# PCB_STM32.net
KiCad netlist of a schematic drawn in Altium Designer
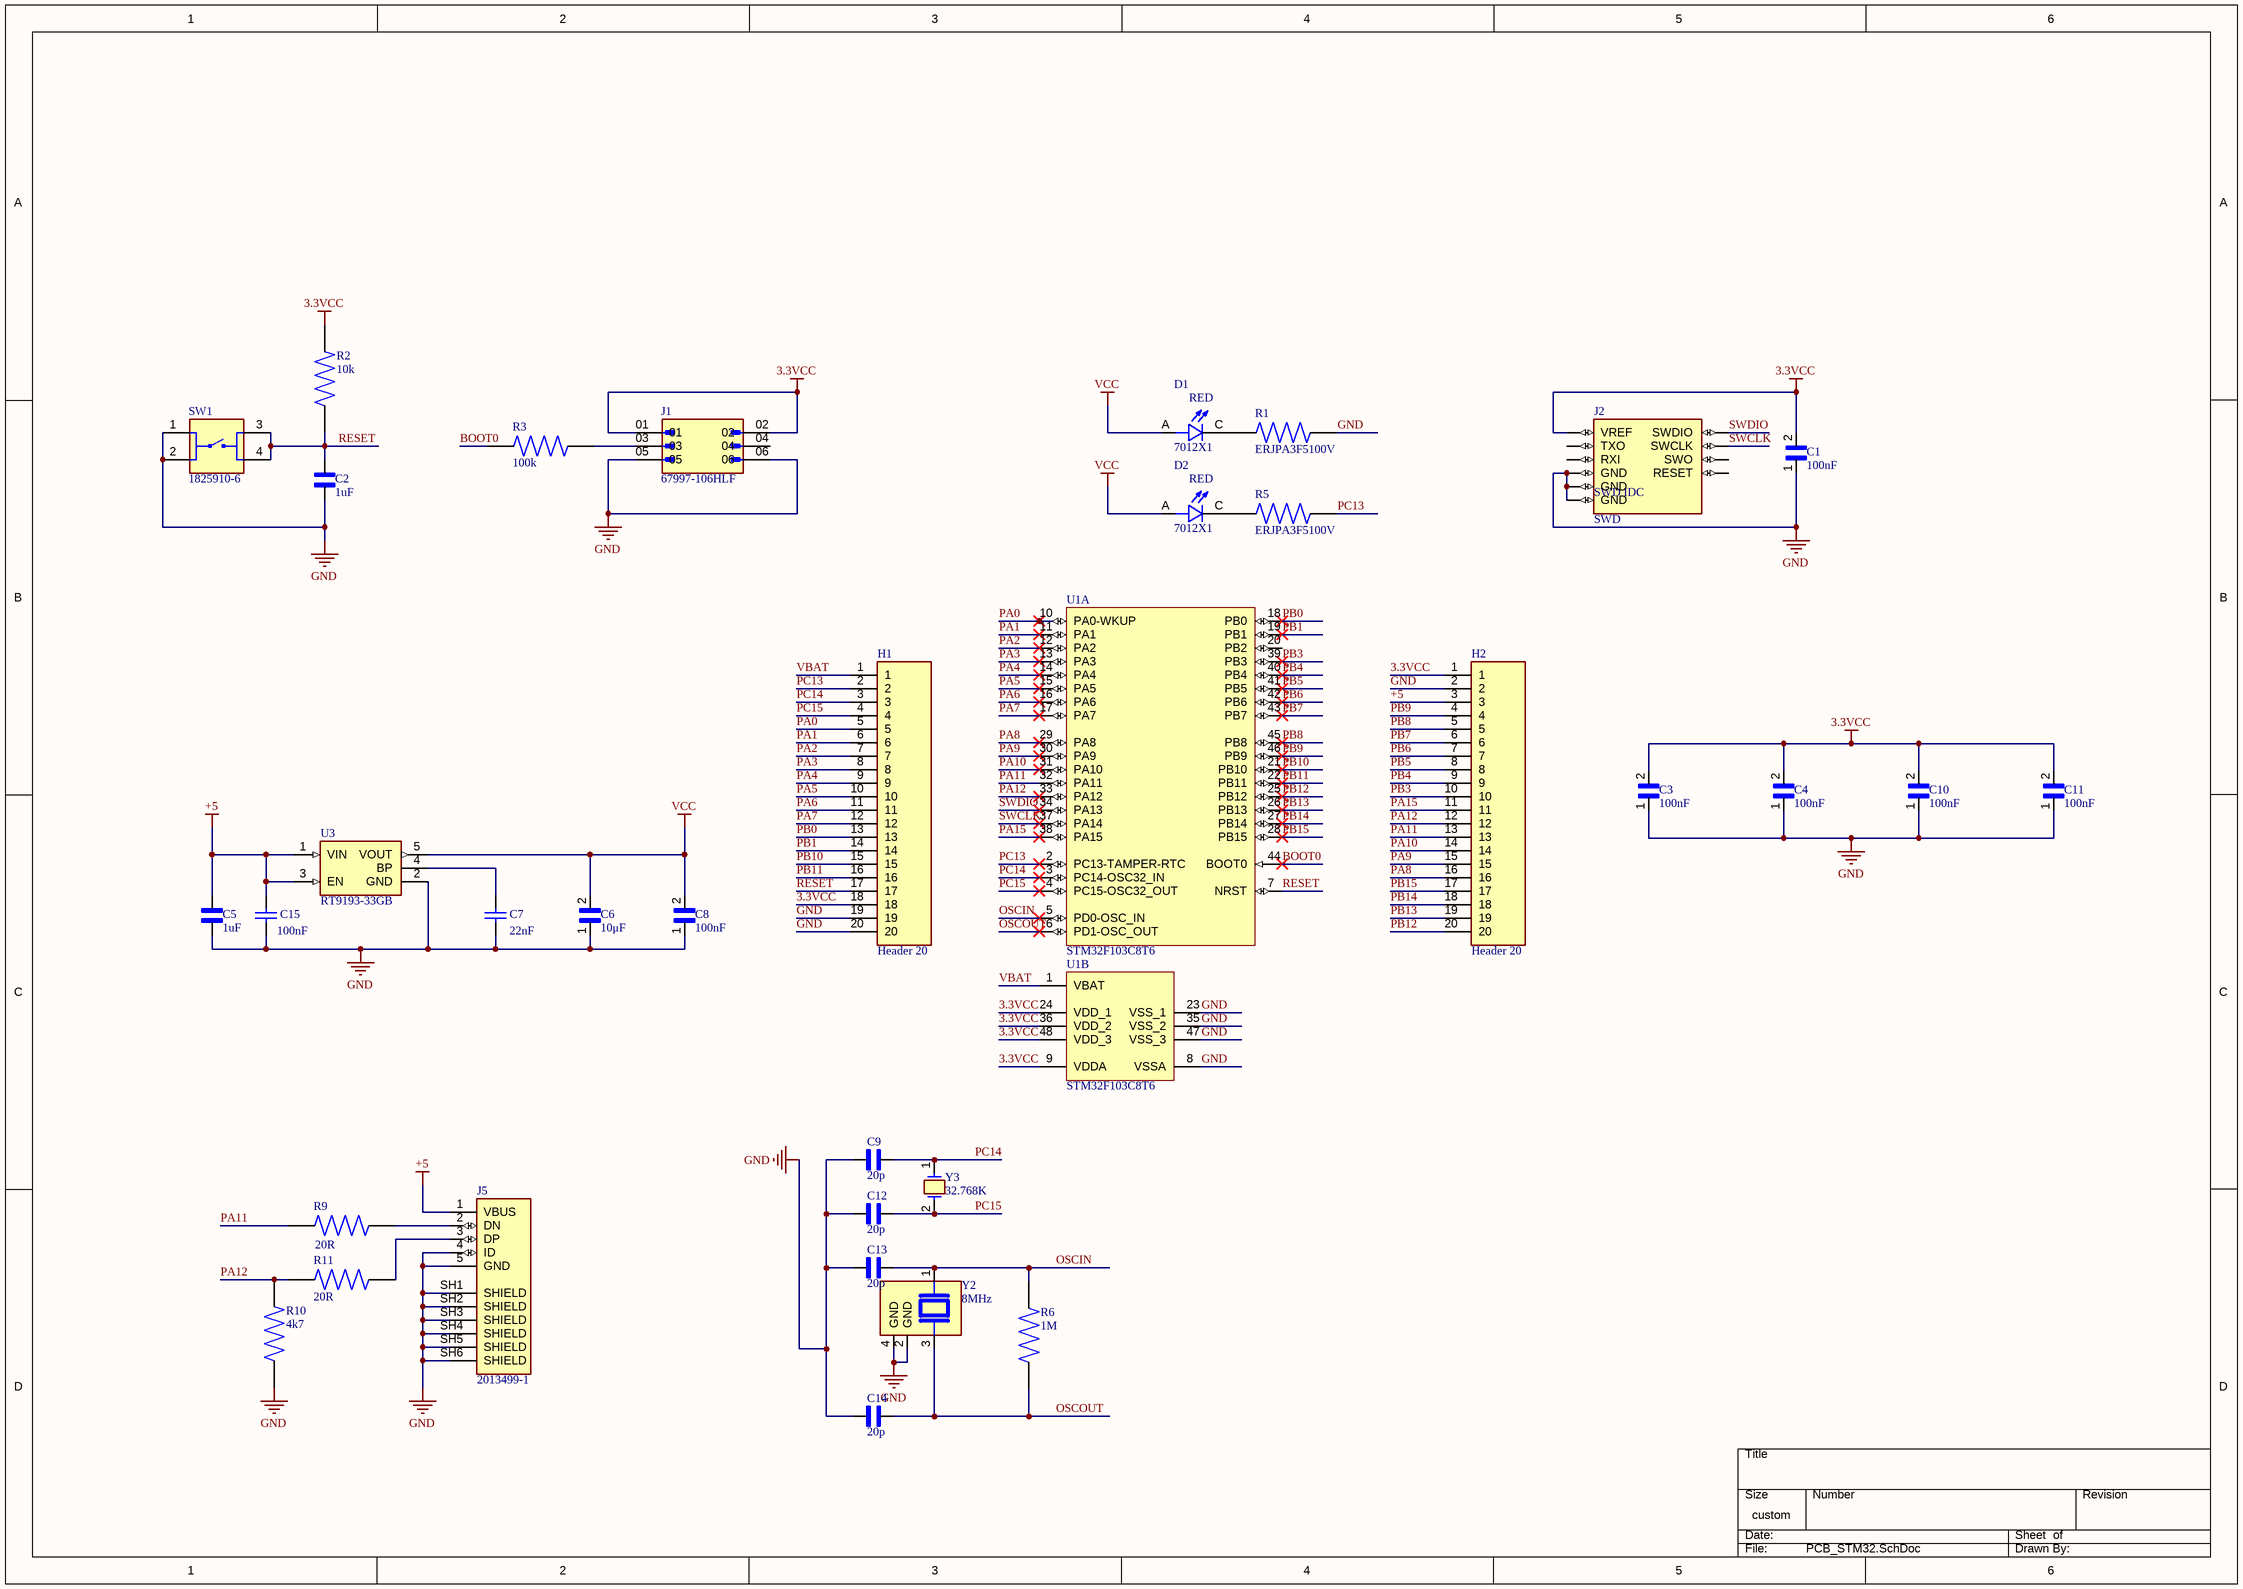
[diagram p0: PCB_STM32.SchDoc]

(export (version "E")
  (design (tool "Eeschema 10.0.6"))
  (components
    (comp (ref "C1")
      (value "100nF")
      (footprint "WCAP-CSGP_0201_L0.6W0.3H0.3")
      (description "0.1 ÂµF Â±10% 50V Ceramic Capacitor X7R 0805 (2012 Metric)")
      (fields (field (name "MP") "C2012X7R1H104K085AA") (field (name "MF") "TDK"))
      (libsource (lib "Cap01u") (part "C2012X7R1H104K085AA"))
    )
    (comp (ref "C2")
      (value "1uF")
      (footprint "CAPC1608X55N")
      (description "Cap Ceramic 1uF 10V X6S 10% SMD 0603 105Â°C Punched Paper T/R")
      (fields (field (name "MF") "TDK") (field (name "MP") "CGB3B3X6S1A105K055AB"))
      (libsource (lib "Cap1u") (part "CGB3B3X6S1A105K055AB"))
    )
    (comp (ref "C3")
      (value "100nF")
      (footprint "WCAP-CSGP_0201_L0.6W0.3H0.3")
      (description "0.1 ÂµF Â±10% 50V Ceramic Capacitor X7R 0805 (2012 Metric)")
      (fields (field (name "MP") "C2012X7R1H104K085AA") (field (name "MF") "TDK"))
      (libsource (lib "Cap01u") (part "C2012X7R1H104K085AA"))
    )
    (comp (ref "C4")
      (value "100nF")
      (footprint "WCAP-CSGP_0201_L0.6W0.3H0.3")
      (description "0.1 ÂµF Â±10% 50V Ceramic Capacitor X7R 0805 (2012 Metric)")
      (fields (field (name "MP") "C2012X7R1H104K085AA") (field (name "MF") "TDK"))
      (libsource (lib "Cap01u") (part "C2012X7R1H104K085AA"))
    )
    (comp (ref "C5")
      (value "1uF")
      (footprint "CAPC1608X55N")
      (description "Cap Ceramic 1uF 10V X6S 10% SMD 0603 105Â°C Punched Paper T/R")
      (fields (field (name "MF") "TDK") (field (name "MP") "CGB3B3X6S1A105K055AB"))
      (libsource (lib "Cap1u") (part "CGB3B3X6S1A105K055AB"))
    )
    (comp (ref "C6")
      (value "10μF")
      (footprint "WCAP-CSGP_0402_L1W0.5H0.5")
      (description "10ÂµF Â±20% 16V Ceramic Capacitor X5R 0805 (2012 Metric)")
      (fields (field (name "MF") "TDK") (field (name "MP") "C2012X5R1C106M085AC"))
      (libsource (lib "Cap10u") (part "C2012X5R1C106M085AC"))
    )
    (comp (ref "C7")
      (value "22nF")
      (footprint "WCAP-CSGP_1206_L3.2W1.6H1.6")
      (description "WCAP-CSGP Multilayer Ceramic Chip Capacitor, General Purpose, size 1206, NP0, 22nF, 10V")
      (fields
        (field (name "MANUFACTURER PART NUMBER") "885012008009")
        (field (name "MANUFACTURER") "Wurth Elektronik")
      )
      (libsource (lib "Cap100n") (part "885012008009"))
    )
    (comp (ref "C8")
      (value "100nF")
      (footprint "WCAP-CSGP_0201_L0.6W0.3H0.3")
      (description "0.1 ÂµF Â±10% 50V Ceramic Capacitor X7R 0805 (2012 Metric)")
      (fields (field (name "MP") "C2012X7R1H104K085AA") (field (name "MF") "TDK"))
      (libsource (lib "Cap01u") (part "C2012X7R1H104K085AA"))
    )
    (comp (ref "C9")
      (value "20p")
      (footprint "CAPC0603X33N")
      (description "SMD capacitor C0G(EIA) with capacitance 20pF Tol.5%. Rated voltage 50Vdc 125C")
      (fields (field (name "MF") "Murata Electronics") (field (name "MP") "GRM0335C1H200JA01D"))
      (libsource (lib "Cap20pF") (part "GRM0335C1H200JA01D"))
    )
    (comp (ref "C10")
      (value "100nF")
      (footprint "WCAP-CSGP_0201_L0.6W0.3H0.3")
      (description "0.1 ÂµF Â±10% 50V Ceramic Capacitor X7R 0805 (2012 Metric)")
      (fields (field (name "MP") "C2012X7R1H104K085AA") (field (name "MF") "TDK"))
      (libsource (lib "Cap01u") (part "C2012X7R1H104K085AA"))
    )
    (comp (ref "C11")
      (value "100nF")
      (footprint "WCAP-CSGP_0201_L0.6W0.3H0.3")
      (description "0.1 ÂµF Â±10% 50V Ceramic Capacitor X7R 0805 (2012 Metric)")
      (fields (field (name "MP") "C2012X7R1H104K085AA") (field (name "MF") "TDK"))
      (libsource (lib "Cap01u") (part "C2012X7R1H104K085AA"))
    )
    (comp (ref "C12")
      (value "20p")
      (footprint "CAPC0603X33N")
      (description "SMD capacitor C0G(EIA) with capacitance 20pF Tol.5%. Rated voltage 50Vdc 125C")
      (fields (field (name "MF") "Murata Electronics") (field (name "MP") "GRM0335C1H200JA01D"))
      (libsource (lib "Cap20pF") (part "GRM0335C1H200JA01D"))
    )
    (comp (ref "C13")
      (value "20p")
      (footprint "CAPC0603X33N")
      (description "SMD capacitor C0G(EIA) with capacitance 20pF Tol.5%. Rated voltage 50Vdc 125C")
      (fields (field (name "MF") "Murata Electronics") (field (name "MP") "GRM0335C1H200JA01D"))
      (libsource (lib "Cap20pF") (part "GRM0335C1H200JA01D"))
    )
    (comp (ref "C14")
      (value "20p")
      (footprint "CAPC0603X33N")
      (description "SMD capacitor C0G(EIA) with capacitance 20pF Tol.5%. Rated voltage 50Vdc 125C")
      (fields (field (name "MF") "Murata Electronics") (field (name "MP") "GRM0335C1H200JA01D"))
      (libsource (lib "Cap20pF") (part "GRM0335C1H200JA01D"))
    )
    (comp (ref "C15")
      (value "100nF")
      (footprint "WCAP-CSGP_0201_L0.6W0.3H0.3")
      (description "WCAP-CSGP Multilayer Ceramic Chip Capacitor, General Purpose, size 0201, X5R Class II, 100nF, 16V")
      (fields
        (field (name "MANUFACTURER PART NUMBER") "885012104001")
        (field (name "MANUFACTURER") "Wurth Elektronik")
      )
      (libsource (lib "Cap100n") (part "885012104001"))
    )
    (comp (ref "D1")
      (value "7012X1")
      (footprint "LED_7012X1")
      (description "Red - LED Indication - Discrete 1.7V 0805 (2012 Metric)")
      (fields (field (name "MF") "VCC"))
      (libsource (lib "RedLed") (part "7012X1"))
    )
    (comp (ref "D2")
      (value "7012X1")
      (footprint "LED_7012X1")
      (description "Red - LED Indication - Discrete 1.7V 0805 (2012 Metric)")
      (fields (field (name "MF") "VCC"))
      (libsource (lib "RedLed") (part "7012X1"))
    )
    (comp (ref "H1")
      (value "Header 20")
      (footprint "TE_2-640456-0")
      (description "Header Friction Lock MTA-100 20 250VAC Polyester Tin Copper Alloy Tin ¦ TE Connectivity 2-640456-0")
      (fields (field (name "MF") "TE Connectivity") (field (name "MP") "2-640456-0"))
      (libsource (lib "Header20") (part "2-640456-0"))
    )
    (comp (ref "H2")
      (value "Header 20")
      (footprint "TE_2-640456-0")
      (description "Header Friction Lock MTA-100 20 250VAC Polyester Tin Copper Alloy Tin ¦ TE Connectivity 2-640456-0")
      (fields (field (name "MF") "TE Connectivity") (field (name "MP") "2-640456-0"))
      (libsource (lib "Header20") (part "2-640456-0"))
    )
    (comp (ref "J1")
      (value "67997-106HLF")
      (footprint "AMPHENOL_67997-106HLF")
      (fields (field (name "MF") "Amphenol ICC"))
      (libsource (lib "Header3x2") (part "67997-106HLF"))
    )
    (comp (ref "J2")
      (value "SWD")
      (footprint "ARM-JTAG-10-SWD-IDC")
      (description "DEBUG ADAPTER FOR ARM-USB-TINY-H")
      (fields (field (name "MF") "Olimex LTD") (field (name "MP") "ARM-JTAG-SWD"))
      (libsource (lib "SWD") (part "ARM-JTAG-SWD"))
    )
    (comp (ref "J5")
      (value "2013499-1")
      (footprint "TE_2013499-1")
      (libsource (lib "micro USB") (part "2013499-1"))
    )
    (comp (ref "R1")
      (value "ERJPA3F5100V")
      (footprint "RES_ERJPA3F5100V")
      (description "RES, THICK FILM, 510R, 1%, 0.25W, 0603")
      (fields (field (name "MF") "Panasonic") (field (name "MP") "ERJ-PA3F5100V"))
      (libsource (lib "RES510") (part "ERJPA3F5100V"))
    )
    (comp (ref "R2")
      (value "10k")
      (footprint "RESC2012X60N")
      (description "10 kOhms Â±1% 0.125W, 1/8W Chip Resistor 0805 (2012 Metric) Moisture Resistant Thick Film")
      (fields (field (name "MF") "Yageo") (field (name "MP") "RC0805FR-0710KL"))
      (libsource (lib "RES10k") (part "RC0805FR-0710KL"))
    )
    (comp (ref "R3")
      (value "100k")
      (footprint "RESC2012X60N")
      (description "100 kOhms Â±1% 0.125W, 1/8W Chip Resistor 0805 (2012 Metric) Moisture Resistant Thick Film")
      (fields (field (name "MF") "Yageo") (field (name "MP") "RC0805FR-07100KL"))
      (libsource (lib "RES100k") (part "RC0805FR-07100KL"))
    )
    (comp (ref "R5")
      (value "ERJPA3F5100V")
      (footprint "RES_ERJPA3F5100V")
      (description "RES, THICK FILM, 510R, 1%, 0.25W, 0603")
      (fields (field (name "MF") "Panasonic") (field (name "MP") "ERJ-PA3F5100V"))
      (libsource (lib "RES510") (part "ERJPA3F5100V"))
    )
    (comp (ref "R6")
      (value "1M")
      (footprint "RESC2012X60N")
      (description "1 MOhms Â±1% 0.125W, 1/8W Chip Resistor 0805 (2012 Metric) Moisture Resistant Thick Film")
      (fields (field (name "MF") "Yageo") (field (name "MP") "RC0805FR-071ML"))
      (libsource (lib "RES1M") (part "RC0805FR-071ML"))
    )
    (comp (ref "R9")
      (value "20R")
      (footprint "RESC5025X120N")
      (fields (field (name "MP") "3-2176397-2"))
      (libsource (lib "RES20") (part "3-2176397-2"))
    )
    (comp (ref "R10")
      (value "4k7")
      (footprint "RESC1608X55N")
      (fields
        (field (name "MF") "TE Connectivity")
        (field (name "MP") "CRG0603F4K7")
        (field (name "TOLERANCE") "1%")
      )
      (libsource (lib "RES4.7k") (part "CRG0603F4K7"))
    )
    (comp (ref "R11")
      (value "20R")
      (footprint "RESC5025X120N")
      (fields (field (name "MP") "3-2176397-2"))
      (libsource (lib "RES20") (part "3-2176397-2"))
    )
    (comp (ref "SW1")
      (value "1825910-6")
      (footprint "SW_1825910-6-4")
      (description "Switch Push Button OFF (ON) SPST Round Button 0.05A 24VDC Momentary Contact PC Pins Thru-Hole")
      (fields (field (name "MF") "TE Connectivity") (field (name "DIGI-KEY_PART_NUMBER") "450-1650-ND"))
      (libsource (lib "Button") (part "1825910-6"))
    )
    (comp (ref "U1")
      (value "STM32F103C8T6")
      (footprint "STM-LQFP48_L")
      (libsource (lib "STM32") (part "CMP-0237-00215-3"))
    )
    (comp (ref "U3")
      (value "RT9193-33GB")
      (footprint "SOT94P279X129-5N")
      (description "Linear Voltage Regulator IC Positive Fixed 1 Output 300mA TSOT-23-5")
      (fields (field (name "MF") "Richtek USA") (field (name "DIGI-KEY_PART_NUMBER") "1028-1014-2-ND"))
      (libsource (lib "RT9193-33GB") (part "RT9193-33GB"))
    )
    (comp (ref "Y2")
      (value "8MHz")
      (footprint "XTAL_ABM3B-8.000MHZ-10-1-U-T")
      (description "8 MHz Â±10ppm Crystal 10pF 200 Ohms 4-SMD, No Lead")
      (fields (field (name "MF") "Abracon") (field (name "MP") "ABM3B-8.000MHZ-10-1-U-T"))
      (libsource (lib "Crystal 8MHz") (part "ABM3B-8.000MHZ-10-1-U-T"))
    )
    (comp (ref "Y3")
      (value "32.768K")
      (footprint "XTAL_NX3215SA-32.768K-STD-MUA-14")
      (description "32.768kHz Â±20ppm Crystal 6pF 70 kOhms 2-SMD, No Lead  MANUFACTURER: NIHON DEMPA KOGYO")
      (fields (field (name "MP") "NX3215SA-32.768K-STD-MUA-14"))
      (libsource (lib "Crystal 32.768k") (part "NX3215SA-32.768K-STD-MUA-14"))
    )
  )
  (nets
    (net (code "1") (name "+5") (class "Default")
      (node (ref "C15") (pin "2") (pinfunction "2_2") (pintype "passive"))
      (node (ref "C5") (pin "1") (pinfunction "1_1") (pintype "passive"))
      (node (ref "H2") (pin "3") (pinfunction "3_3") (pintype "passive"))
      (node (ref "J5") (pin "1") (pinfunction "VBUS_1") (pintype "power_in"))
      (node (ref "U3") (pin "1") (pinfunction "VIN_1") (pintype "input"))
      (node (ref "U3") (pin "3") (pinfunction "EN_3") (pintype "input"))
    )
    (net (code "2") (name "/BOOT0") (class "Default")
      (node (ref "R3") (pin "1") (pinfunction "1_1") (pintype "passive"))
      (node (ref "U1") (pin "44") (pinfunction "BOOT0_44") (pintype "input"))
    )
    (net (code "3") (name "/OSCIN") (class "Default")
      (node (ref "C13") (pin "2") (pinfunction "2_2") (pintype "passive"))
      (node (ref "R6") (pin "2") (pinfunction "2_2") (pintype "passive"))
      (node (ref "U1") (pin "5") (pinfunction "PD0-OSC_IN_5") (pintype "bidirectional"))
      (node (ref "Y2") (pin "1") (pinfunction "1_1") (pintype "passive"))
    )
    (net (code "4") (name "/OSCOUT") (class "Default")
      (node (ref "C14") (pin "2") (pinfunction "2_2") (pintype "passive"))
      (node (ref "R6") (pin "1") (pinfunction "1_1") (pintype "passive"))
      (node (ref "U1") (pin "6") (pinfunction "PD1-OSC_OUT_6") (pintype "bidirectional"))
      (node (ref "Y2") (pin "3") (pinfunction "2_3") (pintype "passive"))
    )
    (net (code "5") (name "/PA0") (class "Default")
      (node (ref "H1") (pin "5") (pinfunction "5_5") (pintype "passive"))
      (node (ref "U1") (pin "10") (pinfunction "PA0-WKUP_10") (pintype "bidirectional"))
    )
    (net (code "6") (name "/PA1") (class "Default")
      (node (ref "H1") (pin "6") (pinfunction "6_6") (pintype "passive"))
      (node (ref "U1") (pin "11") (pinfunction "PA1_11") (pintype "bidirectional"))
    )
    (net (code "7") (name "/PA2") (class "Default")
      (node (ref "H1") (pin "7") (pinfunction "7_7") (pintype "passive"))
      (node (ref "U1") (pin "12") (pinfunction "PA2_12") (pintype "bidirectional"))
    )
    (net (code "8") (name "/PA3") (class "Default")
      (node (ref "H1") (pin "8") (pinfunction "8_8") (pintype "passive"))
      (node (ref "U1") (pin "13") (pinfunction "PA3_13") (pintype "bidirectional"))
    )
    (net (code "9") (name "/PA4") (class "Default")
      (node (ref "H1") (pin "9") (pinfunction "9_9") (pintype "passive"))
      (node (ref "U1") (pin "14") (pinfunction "PA4_14") (pintype "bidirectional"))
    )
    (net (code "10") (name "/PA5") (class "Default")
      (node (ref "H1") (pin "10") (pinfunction "10_10") (pintype "passive"))
      (node (ref "U1") (pin "15") (pinfunction "PA5_15") (pintype "bidirectional"))
    )
    (net (code "11") (name "/PA6") (class "Default")
      (node (ref "H1") (pin "11") (pinfunction "11_11") (pintype "passive"))
      (node (ref "U1") (pin "16") (pinfunction "PA6_16") (pintype "bidirectional"))
    )
    (net (code "12") (name "/PA7") (class "Default")
      (node (ref "H1") (pin "12") (pinfunction "12_12") (pintype "passive"))
      (node (ref "U1") (pin "17") (pinfunction "PA7_17") (pintype "bidirectional"))
    )
    (net (code "13") (name "/PA8") (class "Default")
      (node (ref "H2") (pin "16") (pinfunction "16_16") (pintype "passive"))
      (node (ref "U1") (pin "29") (pinfunction "PA8_29") (pintype "bidirectional"))
    )
    (net (code "14") (name "/PA9") (class "Default")
      (node (ref "H2") (pin "15") (pinfunction "15_15") (pintype "passive"))
      (node (ref "U1") (pin "30") (pinfunction "PA9_30") (pintype "bidirectional"))
    )
    (net (code "15") (name "/PA10") (class "Default")
      (node (ref "H2") (pin "14") (pinfunction "14_14") (pintype "passive"))
      (node (ref "U1") (pin "31") (pinfunction "PA10_31") (pintype "bidirectional"))
    )
    (net (code "16") (name "/PA11") (class "Default")
      (node (ref "H2") (pin "13") (pinfunction "13_13") (pintype "passive"))
      (node (ref "R9") (pin "1") (pinfunction "1_1") (pintype "passive"))
      (node (ref "U1") (pin "32") (pinfunction "PA11_32") (pintype "bidirectional"))
    )
    (net (code "17") (name "/PA12") (class "Default")
      (node (ref "H2") (pin "12") (pinfunction "12_12") (pintype "passive"))
      (node (ref "R10") (pin "2") (pinfunction "2_2") (pintype "passive"))
      (node (ref "R11") (pin "1") (pinfunction "1_1") (pintype "passive"))
      (node (ref "U1") (pin "33") (pinfunction "PA12_33") (pintype "bidirectional"))
    )
    (net (code "18") (name "/PA15") (class "Default")
      (node (ref "H2") (pin "11") (pinfunction "11_11") (pintype "passive"))
      (node (ref "U1") (pin "38") (pinfunction "PA15_38") (pintype "bidirectional"))
    )
    (net (code "19") (name "/PB0") (class "Default")
      (node (ref "H1") (pin "13") (pinfunction "13_13") (pintype "passive"))
      (node (ref "U1") (pin "18") (pinfunction "PB0_18") (pintype "bidirectional"))
    )
    (net (code "20") (name "/PB1") (class "Default")
      (node (ref "H1") (pin "14") (pinfunction "14_14") (pintype "passive"))
      (node (ref "U1") (pin "19") (pinfunction "PB1_19") (pintype "bidirectional"))
    )
    (net (code "21") (name "/PB3") (class "Default")
      (node (ref "H2") (pin "10") (pinfunction "10_10") (pintype "passive"))
      (node (ref "U1") (pin "39") (pinfunction "PB3_39") (pintype "bidirectional"))
    )
    (net (code "22") (name "/PB4") (class "Default")
      (node (ref "H2") (pin "9") (pinfunction "9_9") (pintype "passive"))
      (node (ref "U1") (pin "40") (pinfunction "PB4_40") (pintype "bidirectional"))
    )
    (net (code "23") (name "/PB5") (class "Default")
      (node (ref "H2") (pin "8") (pinfunction "8_8") (pintype "passive"))
      (node (ref "U1") (pin "41") (pinfunction "PB5_41") (pintype "bidirectional"))
    )
    (net (code "24") (name "/PB6") (class "Default")
      (node (ref "H2") (pin "7") (pinfunction "7_7") (pintype "passive"))
      (node (ref "U1") (pin "42") (pinfunction "PB6_42") (pintype "bidirectional"))
    )
    (net (code "25") (name "/PB7") (class "Default")
      (node (ref "H2") (pin "6") (pinfunction "6_6") (pintype "passive"))
      (node (ref "U1") (pin "43") (pinfunction "PB7_43") (pintype "bidirectional"))
    )
    (net (code "26") (name "/PB8") (class "Default")
      (node (ref "H2") (pin "5") (pinfunction "5_5") (pintype "passive"))
      (node (ref "U1") (pin "45") (pinfunction "PB8_45") (pintype "bidirectional"))
    )
    (net (code "27") (name "/PB9") (class "Default")
      (node (ref "H2") (pin "4") (pinfunction "4_4") (pintype "passive"))
      (node (ref "U1") (pin "46") (pinfunction "PB9_46") (pintype "bidirectional"))
    )
    (net (code "28") (name "/PB10") (class "Default")
      (node (ref "H1") (pin "15") (pinfunction "15_15") (pintype "passive"))
      (node (ref "U1") (pin "21") (pinfunction "PB10_21") (pintype "bidirectional"))
    )
    (net (code "29") (name "/PB11") (class "Default")
      (node (ref "H1") (pin "16") (pinfunction "16_16") (pintype "passive"))
      (node (ref "U1") (pin "22") (pinfunction "PB11_22") (pintype "bidirectional"))
    )
    (net (code "30") (name "/PB12") (class "Default")
      (node (ref "H2") (pin "20") (pinfunction "20_20") (pintype "passive"))
      (node (ref "U1") (pin "25") (pinfunction "PB12_25") (pintype "bidirectional"))
    )
    (net (code "31") (name "/PB13") (class "Default")
      (node (ref "H2") (pin "19") (pinfunction "19_19") (pintype "passive"))
      (node (ref "U1") (pin "26") (pinfunction "PB13_26") (pintype "bidirectional"))
    )
    (net (code "32") (name "/PB14") (class "Default")
      (node (ref "H2") (pin "18") (pinfunction "18_18") (pintype "passive"))
      (node (ref "U1") (pin "27") (pinfunction "PB14_27") (pintype "bidirectional"))
    )
    (net (code "33") (name "/PB15") (class "Default")
      (node (ref "H2") (pin "17") (pinfunction "17_17") (pintype "passive"))
      (node (ref "U1") (pin "28") (pinfunction "PB15_28") (pintype "bidirectional"))
    )
    (net (code "34") (name "/PC13") (class "Default")
      (node (ref "H1") (pin "2") (pinfunction "2_2") (pintype "passive"))
      (node (ref "R5") (pin "2") (pinfunction "2_2") (pintype "passive"))
      (node (ref "U1") (pin "2") (pinfunction "PC13-TAMPER-RTC_2") (pintype "bidirectional"))
    )
    (net (code "35") (name "/PC14") (class "Default")
      (node (ref "C9") (pin "2") (pinfunction "2_2") (pintype "passive"))
      (node (ref "H1") (pin "3") (pinfunction "3_3") (pintype "passive"))
      (node (ref "U1") (pin "3") (pinfunction "PC14-OSC32_IN_3") (pintype "bidirectional"))
      (node (ref "Y3") (pin "1") (pinfunction "1_1") (pintype "passive"))
    )
    (net (code "36") (name "/PC15") (class "Default")
      (node (ref "C12") (pin "2") (pinfunction "2_2") (pintype "passive"))
      (node (ref "H1") (pin "4") (pinfunction "4_4") (pintype "passive"))
      (node (ref "U1") (pin "4") (pinfunction "PC15-OSC32_OUT_4") (pintype "bidirectional"))
      (node (ref "Y3") (pin "2") (pinfunction "2_2") (pintype "passive"))
    )
    (net (code "37") (name "/RESET") (class "Default")
      (node (ref "C2") (pin "1") (pinfunction "1_1") (pintype "passive"))
      (node (ref "H1") (pin "17") (pinfunction "17_17") (pintype "passive"))
      (node (ref "R2") (pin "2") (pinfunction "2_2") (pintype "passive"))
      (node (ref "SW1") (pin "3") (pinfunction "3_3") (pintype "passive"))
      (node (ref "SW1") (pin "4") (pinfunction "4_4") (pintype "passive"))
      (node (ref "U1") (pin "7") (pinfunction "NRST_7") (pintype "bidirectional"))
    )
    (net (code "38") (name "/SWCLK") (class "Default")
      (node (ref "J2") (pin "SWCLK") (pinfunction "SWCLK_SWCLK") (pintype "bidirectional"))
      (node (ref "U1") (pin "37") (pinfunction "PA14_37") (pintype "bidirectional"))
    )
    (net (code "39") (name "/SWDIO") (class "Default")
      (node (ref "J2") (pin "SWDIO") (pinfunction "SWDIO_SWDIO") (pintype "bidirectional"))
      (node (ref "U1") (pin "34") (pinfunction "PA13_34") (pintype "bidirectional"))
    )
    (net (code "40") (name "/VBAT") (class "Default")
      (node (ref "H1") (pin "1") (pinfunction "1_1") (pintype "passive"))
      (node (ref "U1") (pin "1") (pinfunction "VBAT_1") (pintype "power_in"))
    )
    (net (code "41") (name "3.3VCC") (class "Default")
      (node (ref "C1") (pin "2") (pinfunction "2_2") (pintype "passive"))
      (node (ref "C10") (pin "2") (pinfunction "2_2") (pintype "passive"))
      (node (ref "C11") (pin "2") (pinfunction "2_2") (pintype "passive"))
      (node (ref "C3") (pin "2") (pinfunction "2_2") (pintype "passive"))
      (node (ref "C4") (pin "2") (pinfunction "2_2") (pintype "passive"))
      (node (ref "H1") (pin "18") (pinfunction "18_18") (pintype "passive"))
      (node (ref "H2") (pin "1") (pinfunction "1_1") (pintype "passive"))
      (node (ref "J1") (pin "01") (pinfunction "01_01") (pintype "passive"))
      (node (ref "J1") (pin "02") (pinfunction "02_02") (pintype "passive"))
      (node (ref "J2") (pin "VREF") (pinfunction "VREF_VREF") (pintype "bidirectional"))
      (node (ref "R2") (pin "1") (pinfunction "1_1") (pintype "passive"))
      (node (ref "U1") (pin "24") (pinfunction "VDD_1_24") (pintype "power_in"))
      (node (ref "U1") (pin "36") (pinfunction "VDD_2_36") (pintype "power_in"))
      (node (ref "U1") (pin "48") (pinfunction "VDD_3_48") (pintype "power_in"))
      (node (ref "U1") (pin "9") (pinfunction "VDDA_9") (pintype "power_in"))
    )
    (net (code "42") (name "GND") (class "Default")
      (node (ref "C1") (pin "1") (pinfunction "1_1") (pintype "passive"))
      (node (ref "C10") (pin "1") (pinfunction "1_1") (pintype "passive"))
      (node (ref "C11") (pin "1") (pinfunction "1_1") (pintype "passive"))
      (node (ref "C12") (pin "1") (pinfunction "1_1") (pintype "passive"))
      (node (ref "C13") (pin "1") (pinfunction "1_1") (pintype "passive"))
      (node (ref "C14") (pin "1") (pinfunction "1_1") (pintype "passive"))
      (node (ref "C15") (pin "1") (pinfunction "1_1") (pintype "passive"))
      (node (ref "C2") (pin "2") (pinfunction "2_2") (pintype "passive"))
      (node (ref "C3") (pin "1") (pinfunction "1_1") (pintype "passive"))
      (node (ref "C4") (pin "1") (pinfunction "1_1") (pintype "passive"))
      (node (ref "C5") (pin "2") (pinfunction "2_2") (pintype "passive"))
      (node (ref "C6") (pin "1") (pinfunction "1_1") (pintype "passive"))
      (node (ref "C7") (pin "1") (pinfunction "1_1") (pintype "passive"))
      (node (ref "C8") (pin "1") (pinfunction "1_1") (pintype "passive"))
      (node (ref "C9") (pin "1") (pinfunction "1_1") (pintype "passive"))
      (node (ref "H1") (pin "19") (pinfunction "19_19") (pintype "passive"))
      (node (ref "H1") (pin "20") (pinfunction "20_20") (pintype "passive"))
      (node (ref "H2") (pin "2") (pinfunction "2_2") (pintype "passive"))
      (node (ref "J1") (pin "05") (pinfunction "05_05") (pintype "passive"))
      (node (ref "J1") (pin "06") (pinfunction "06_06") (pintype "passive"))
      (node (ref "J2") (pin "GND@1") (pinfunction "GND_GND@1") (pintype "bidirectional"))
      (node (ref "J2") (pin "GND@2") (pinfunction "GND_GND@2") (pintype "bidirectional"))
      (node (ref "J2") (pin "GND@3") (pinfunction "GND_GND@3") (pintype "bidirectional"))
      (node (ref "J5") (pin "4") (pinfunction "ID_4") (pintype "bidirectional"))
      (node (ref "J5") (pin "5") (pinfunction "GND_5") (pintype "power_in"))
      (node (ref "J5") (pin "SH1") (pinfunction "SHIELD_SH1") (pintype "passive"))
      (node (ref "J5") (pin "SH2") (pinfunction "SHIELD_SH2") (pintype "passive"))
      (node (ref "J5") (pin "SH3") (pinfunction "SHIELD_SH3") (pintype "passive"))
      (node (ref "J5") (pin "SH4") (pinfunction "SHIELD_SH4") (pintype "passive"))
      (node (ref "J5") (pin "SH5") (pinfunction "SHIELD_SH5") (pintype "passive"))
      (node (ref "J5") (pin "SH6") (pinfunction "SHIELD_SH6") (pintype "passive"))
      (node (ref "R1") (pin "2") (pinfunction "2_2") (pintype "passive"))
      (node (ref "R10") (pin "1") (pinfunction "1_1") (pintype "passive"))
      (node (ref "SW1") (pin "1") (pinfunction "1_1") (pintype "passive"))
      (node (ref "SW1") (pin "2") (pinfunction "2_2") (pintype "passive"))
      (node (ref "U1") (pin "23") (pinfunction "VSS_1_23") (pintype "power_in"))
      (node (ref "U1") (pin "35") (pinfunction "VSS_2_35") (pintype "power_in"))
      (node (ref "U1") (pin "47") (pinfunction "VSS_3_47") (pintype "power_in"))
      (node (ref "U1") (pin "8") (pinfunction "VSSA_8") (pintype "power_in"))
      (node (ref "U3") (pin "2") (pinfunction "GND_2") (pintype "power_in"))
      (node (ref "Y2") (pin "2") (pinfunction "GND_2") (pintype "power_in"))
      (node (ref "Y2") (pin "4") (pinfunction "GND_4") (pintype "power_in"))
    )
    (net (code "43") (name "Net-(D1-PadC)") (class "Default")
      (node (ref "D1") (pin "C") (pinfunction "C_C") (pintype "passive"))
      (node (ref "R1") (pin "1") (pinfunction "1_1") (pintype "passive"))
    )
    (net (code "44") (name "Net-(D2-PadC)") (class "Default")
      (node (ref "D2") (pin "C") (pinfunction "C_C") (pintype "passive"))
      (node (ref "R5") (pin "1") (pinfunction "1_1") (pintype "passive"))
    )
    (net (code "45") (name "Net-(J1-Pad03)") (class "Default")
      (node (ref "J1") (pin "03") (pinfunction "03_03") (pintype "passive"))
      (node (ref "R3") (pin "2") (pinfunction "2_2") (pintype "passive"))
    )
    (net (code "46") (name "Net-(J5-DN)") (class "Default")
      (node (ref "J5") (pin "2") (pinfunction "DN_2") (pintype "bidirectional"))
      (node (ref "R9") (pin "2") (pinfunction "2_2") (pintype "passive"))
    )
    (net (code "47") (name "Net-(J5-DP)") (class "Default")
      (node (ref "J5") (pin "3") (pinfunction "DP_3") (pintype "bidirectional"))
      (node (ref "R11") (pin "2") (pinfunction "2_2") (pintype "passive"))
    )
    (net (code "48") (name "Net-(U3-BP)") (class "Default")
      (node (ref "C7") (pin "2") (pinfunction "2_2") (pintype "passive"))
      (node (ref "U3") (pin "4") (pinfunction "BP_4") (pintype "passive"))
    )
    (net (code "49") (name "VCC") (class "Default")
      (node (ref "C6") (pin "2") (pinfunction "2_2") (pintype "passive"))
      (node (ref "C8") (pin "2") (pinfunction "2_2") (pintype "passive"))
      (node (ref "D1") (pin "A") (pinfunction "A_A") (pintype "passive"))
      (node (ref "D2") (pin "A") (pinfunction "A_A") (pintype "passive"))
      (node (ref "U3") (pin "5") (pinfunction "VOUT_5") (pintype "output"))
    )
    (net (code "50") (name "unconnected-(J1-Pad04)") (class "Default")
      (node (ref "J1") (pin "04") (pinfunction "04_04") (pintype "passive"))
    )
    (net (code "51") (name "unconnected-(J2-PadRESET)") (class "Default")
      (node (ref "J2") (pin "RESET") (pinfunction "RESET_RESET") (pintype "bidirectional"))
    )
    (net (code "52") (name "unconnected-(J2-PadRXI)") (class "Default")
      (node (ref "J2") (pin "RXI") (pinfunction "RXI_RXI") (pintype "bidirectional"))
    )
    (net (code "53") (name "unconnected-(J2-PadSWO)") (class "Default")
      (node (ref "J2") (pin "SWO") (pinfunction "SWO_SWO") (pintype "bidirectional"))
    )
    (net (code "54") (name "unconnected-(J2-PadTXO)") (class "Default")
      (node (ref "J2") (pin "TXO") (pinfunction "TXO_TXO") (pintype "bidirectional"))
    )
    (net (code "55") (name "unconnected-(U1A-PB2-Pad20)") (class "Default")
      (node (ref "U1") (pin "20") (pinfunction "PB2_20") (pintype "bidirectional"))
    )
  )
)
